# MCU.net
KiCad netlist of a schematic drawn in Altium Designer
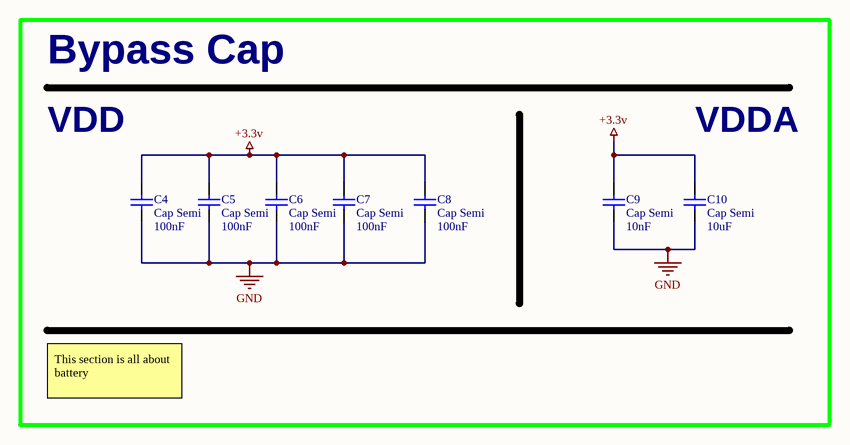
[diagram p0: MCU.SchDoc]

(export (version "E")
  (design (tool "Eeschema 10.0.6"))
  (components
    (comp (ref "C4")
      (value "Cap Semi")
      (footprint "1608[0603]cap")
      (description "Capacitor (Semiconductor SIM Model)")
      (fields (field (name "ALTIUM_VALUE") "100nF") (field (name "PUBLISHER") "Altium Limited"))
      (libsource (lib "smartmcu") (part "Cap Semi"))
    )
    (comp (ref "C5")
      (value "Cap Semi")
      (footprint "1608[0603]cap")
      (description "Capacitor (Semiconductor SIM Model)")
      (fields (field (name "ALTIUM_VALUE") "100nF") (field (name "PUBLISHER") "Altium Limited"))
      (libsource (lib "smartmcu") (part "Cap Semi"))
    )
    (comp (ref "C6")
      (value "Cap Semi")
      (footprint "1608[0603]cap")
      (description "Capacitor (Semiconductor SIM Model)")
      (fields (field (name "ALTIUM_VALUE") "100nF") (field (name "PUBLISHER") "Altium Limited"))
      (libsource (lib "smartmcu") (part "Cap Semi"))
    )
    (comp (ref "C7")
      (value "Cap Semi")
      (footprint "1608[0603]cap")
      (description "Capacitor (Semiconductor SIM Model)")
      (fields (field (name "ALTIUM_VALUE") "100nF") (field (name "PUBLISHER") "Altium Limited"))
      (libsource (lib "smartmcu") (part "Cap Semi"))
    )
    (comp (ref "C8")
      (value "Cap Semi")
      (footprint "1608[0603]cap")
      (description "Capacitor (Semiconductor SIM Model)")
      (fields (field (name "ALTIUM_VALUE") "100nF") (field (name "PUBLISHER") "Altium Limited"))
      (libsource (lib "smartmcu") (part "Cap Semi"))
    )
    (comp (ref "C9")
      (value "Cap Semi")
      (footprint "1608[0603]cap")
      (description "Capacitor (Semiconductor SIM Model)")
      (fields (field (name "ALTIUM_VALUE") "10nF") (field (name "PUBLISHER") "Altium Limited"))
      (libsource (lib "smartmcu") (part "Cap Semi"))
    )
    (comp (ref "C10")
      (value "Cap Semi")
      (footprint "1608[0603]cap")
      (description "Capacitor (Semiconductor SIM Model)")
      (fields (field (name "ALTIUM_VALUE") "10uF") (field (name "PUBLISHER") "Altium Limited"))
      (libsource (lib "smartmcu") (part "Cap Semi"))
    )
  )
  (nets
    (net (code "1") (name "+3.3v") (class "Default")
      (node (ref "C10") (pin "2") (pinfunction "2_2") (pintype "passive"))
      (node (ref "C4") (pin "2") (pinfunction "2_2") (pintype "passive"))
      (node (ref "C5") (pin "2") (pinfunction "2_2") (pintype "passive"))
      (node (ref "C6") (pin "2") (pinfunction "2_2") (pintype "passive"))
      (node (ref "C7") (pin "2") (pinfunction "2_2") (pintype "passive"))
      (node (ref "C8") (pin "2") (pinfunction "2_2") (pintype "passive"))
      (node (ref "C9") (pin "2") (pinfunction "2_2") (pintype "passive"))
    )
    (net (code "2") (name "GND") (class "Default")
      (node (ref "C10") (pin "1") (pinfunction "1_1") (pintype "passive"))
      (node (ref "C4") (pin "1") (pinfunction "1_1") (pintype "passive"))
      (node (ref "C5") (pin "1") (pinfunction "1_1") (pintype "passive"))
      (node (ref "C6") (pin "1") (pinfunction "1_1") (pintype "passive"))
      (node (ref "C7") (pin "1") (pinfunction "1_1") (pintype "passive"))
      (node (ref "C8") (pin "1") (pinfunction "1_1") (pintype "passive"))
      (node (ref "C9") (pin "1") (pinfunction "1_1") (pintype "passive"))
    )
  )
)
